# OLED_096_SH1101A_main.net
KiCad netlist of a schematic drawn in EAGLE
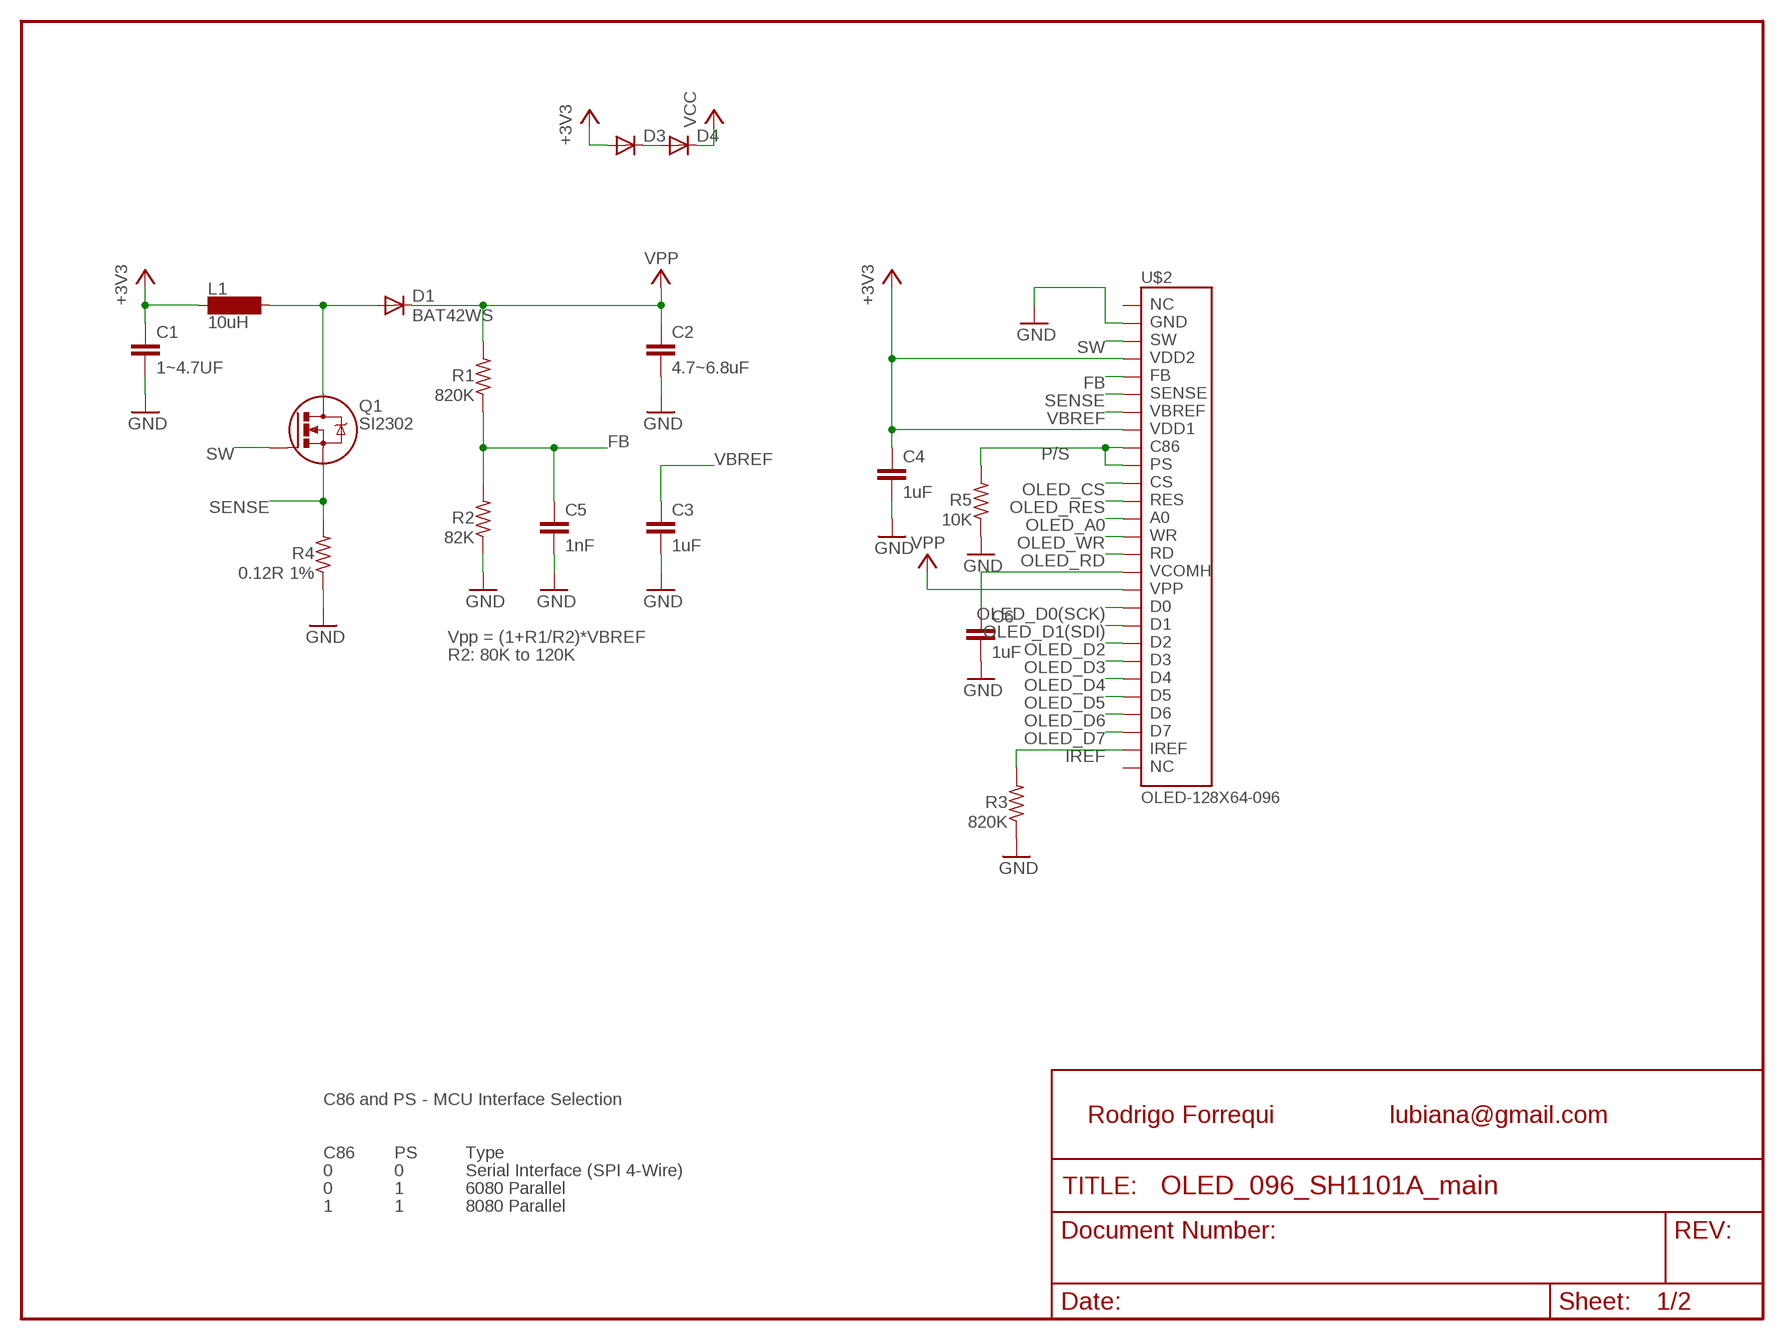
[diagram p0: schematic, sheet 1]
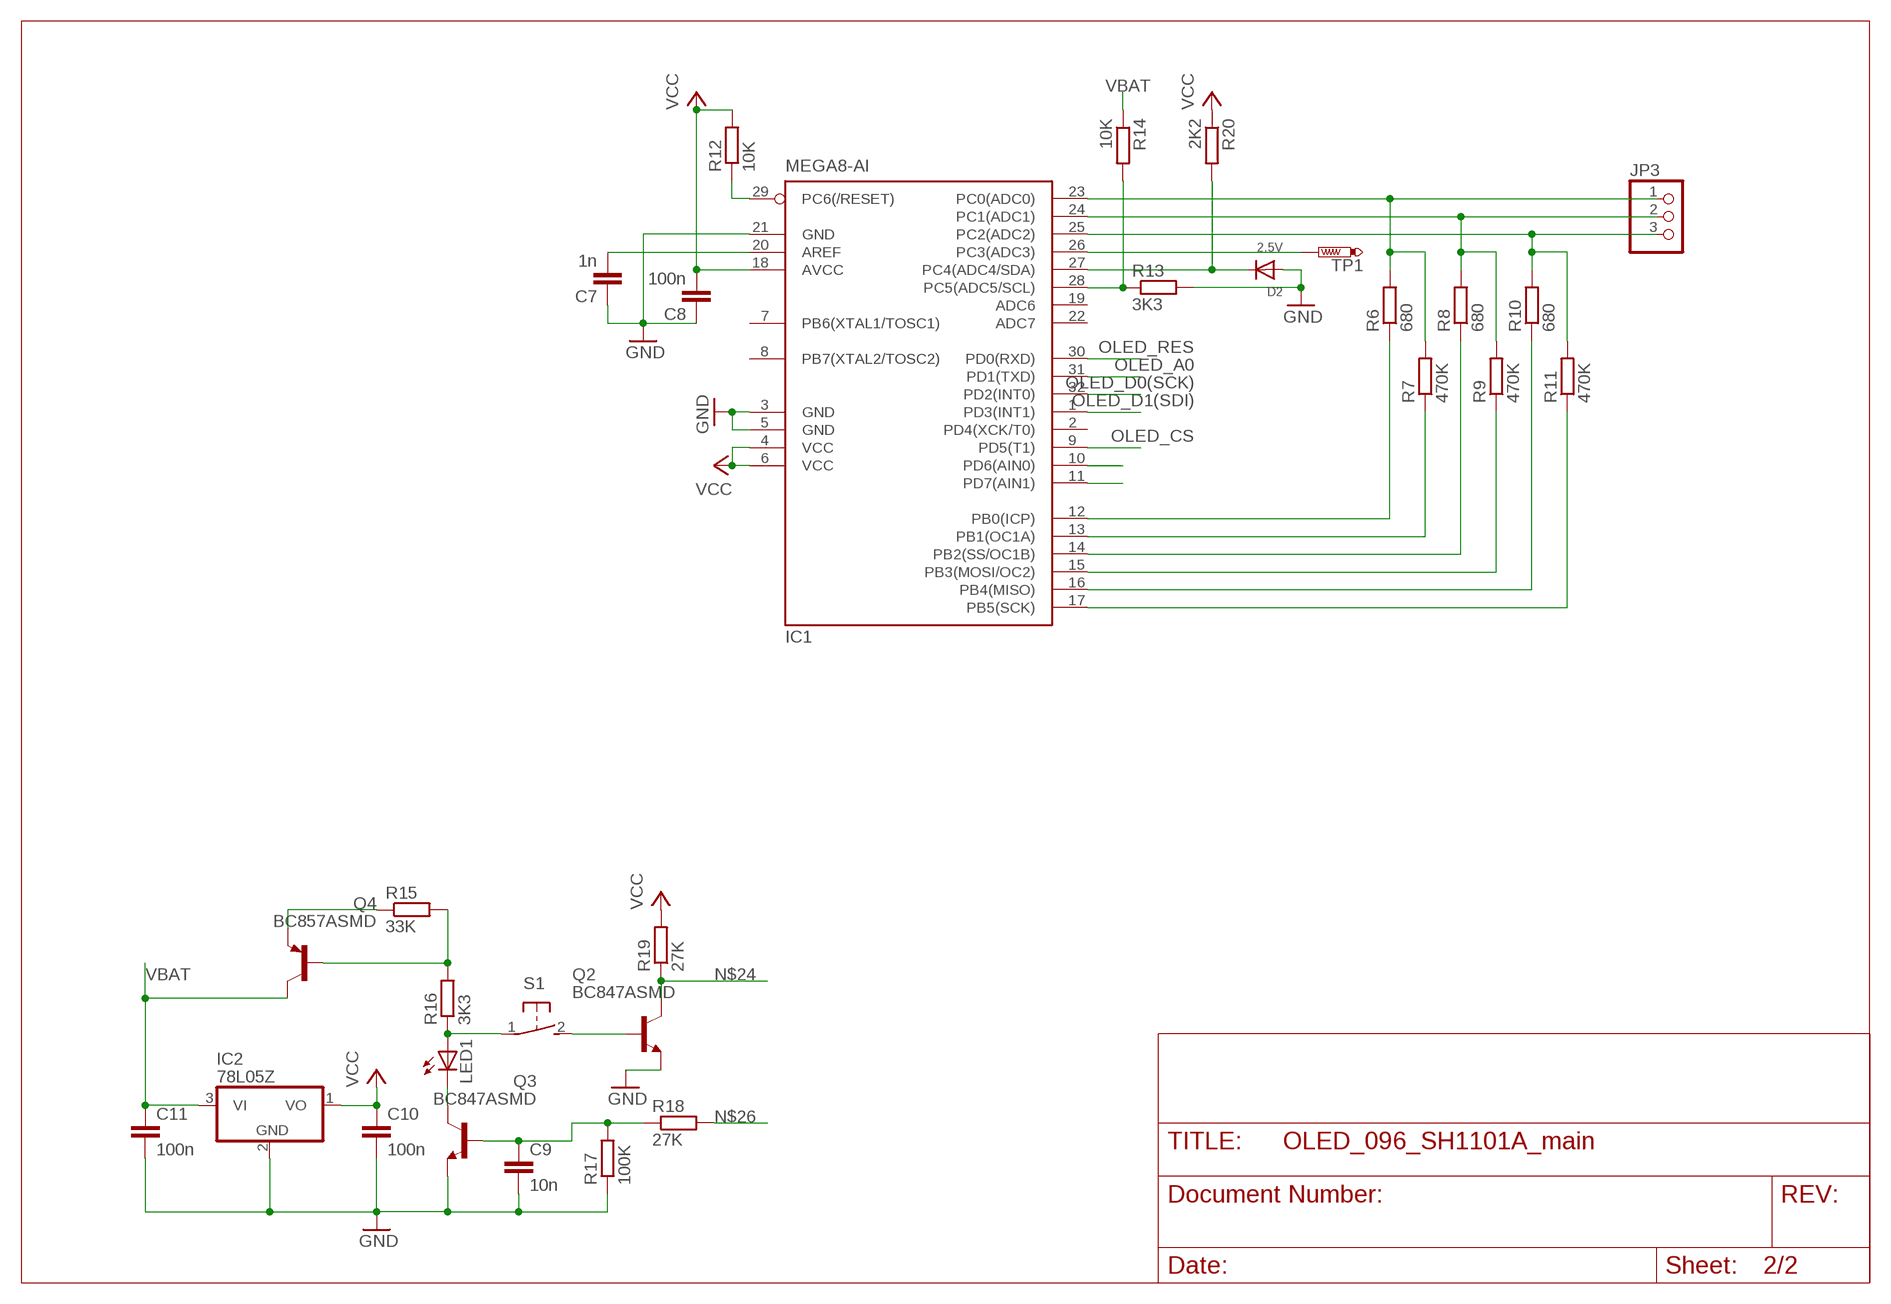
[diagram p1: schematic, sheet 2]

(export (version "E")
  (design (tool "Eeschema 10.0.6"))
  (components
    (comp (ref "C1")
      (value "1~4.7UF")
      (footprint "eagle-import:C0805")
      (libsource (lib "eagle-import") (part "C-EUC0805"))
    )
    (comp (ref "C2")
      (value "4.7~6.8uF")
      (footprint "eagle-import:C0805")
      (libsource (lib "eagle-import") (part "C-EUC0805"))
    )
    (comp (ref "C3")
      (value "1uF")
      (footprint "eagle-import:C0805")
      (libsource (lib "eagle-import") (part "C-EUC0805"))
    )
    (comp (ref "C4")
      (value "1uF")
      (footprint "eagle-import:C0805")
      (libsource (lib "eagle-import") (part "C-EUC0805"))
    )
    (comp (ref "C5")
      (value "1nF")
      (footprint "eagle-import:C0805")
      (libsource (lib "eagle-import") (part "C-EUC0805"))
    )
    (comp (ref "C6")
      (value "1uF")
      (footprint "eagle-import:C0805")
      (libsource (lib "eagle-import") (part "C-EUC0805"))
    )
    (comp (ref "D1")
      (value "BAT42WS")
      (footprint "eagle-import:SOD-323")
      (libsource (lib "eagle-import") (part "DIODESOD"))
    )
    (comp (ref "D3")
      (value "DIODE-MINIMELF")
      (footprint "eagle-import:MINIMELF")
      (libsource (lib "eagle-import") (part "DIODE-MINIMELF"))
    )
    (comp (ref "D4")
      (value "DIODE-MINIMELF")
      (footprint "eagle-import:MINIMELF")
      (libsource (lib "eagle-import") (part "DIODE-MINIMELF"))
    )
    (comp (ref "L1")
      (value "10uH")
      (footprint "eagle-import:LPO4812")
      (libsource (lib "eagle-import") (part "LPO4812"))
    )
    (comp (ref "Q1")
      (value "SI2302")
      (footprint "eagle-import:SOT23-3")
      (libsource (lib "eagle-import") (part "MOSFET-NCHANNELSMD"))
    )
    (comp (ref "R1")
      (value "820K")
      (footprint "eagle-import:R0805")
      (libsource (lib "eagle-import") (part "R-US_R0805"))
    )
    (comp (ref "R2")
      (value "82K")
      (footprint "eagle-import:R0805")
      (libsource (lib "eagle-import") (part "R-US_R0805"))
    )
    (comp (ref "R3")
      (value "820K")
      (footprint "eagle-import:R0805")
      (libsource (lib "eagle-import") (part "R-US_R0805"))
    )
    (comp (ref "R4")
      (value "0.12R 1%")
      (footprint "eagle-import:M1206")
      (libsource (lib "eagle-import") (part "R-US_M1206"))
    )
    (comp (ref "R5")
      (value "10K")
      (footprint "eagle-import:R0805")
      (libsource (lib "eagle-import") (part "R-US_R0805"))
    )
    (comp (ref "U$2")
      (value "OLED-128X64-096")
      (footprint "eagle-import:UG-2864AMBAG01")
      (libsource (lib "eagle-import") (part "OLED-128X64-096"))
    )
    (comp (ref "C7")
      (value "1n")
      (footprint "eagle-import:C0805")
      (libsource (lib "eagle-import") (part "resistor_C-EUC0805"))
    )
    (comp (ref "C8")
      (value "100n")
      (footprint "eagle-import:C0805")
      (libsource (lib "eagle-import") (part "resistor_C-EUC0805"))
    )
    (comp (ref "C9")
      (value "10n")
      (footprint "eagle-import:C0805")
      (libsource (lib "eagle-import") (part "resistor_C-EUC0805"))
    )
    (comp (ref "C10")
      (value "100n")
      (footprint "eagle-import:C0805")
      (libsource (lib "eagle-import") (part "resistor_C-EUC0805"))
    )
    (comp (ref "C11")
      (value "100n")
      (footprint "eagle-import:C0805")
      (libsource (lib "eagle-import") (part "resistor_C-EUC0805"))
    )
    (comp (ref "D2")
      (value "2.5V")
      (footprint "eagle-import:SOD-523")
      (libsource (lib "eagle-import") (part "DIODESOD-523"))
    )
    (comp (ref "IC1")
      (value "MEGA8-AI")
      (footprint "eagle-import:TQFP32-08")
      (fields (field (name "MPN") "ATMEGA8-16AU"))
      (libsource (lib "eagle-import") (part "MEGA8-AI"))
    )
    (comp (ref "IC2")
      (value "78L05Z")
      (footprint "eagle-import:TO92")
      (libsource (lib "eagle-import") (part "78ZL05"))
    )
    (comp (ref "JP3")
      (value "PINHD-1X3")
      (footprint "eagle-import:1X03")
      (libsource (lib "eagle-import") (part "PINHD-1X3"))
    )
    (comp (ref "LED1")
      (value "LEDSML0603")
      (footprint "eagle-import:SML0603")
      (libsource (lib "eagle-import") (part "LEDSML0603"))
    )
    (comp (ref "Q2")
      (value "BC847ASMD")
      (footprint "eagle-import:SOT23")
      (libsource (lib "eagle-import") (part "BC847SMDA"))
    )
    (comp (ref "Q3")
      (value "BC847ASMD")
      (footprint "eagle-import:SOT23")
      (libsource (lib "eagle-import") (part "BC847SMDA"))
    )
    (comp (ref "Q4")
      (value "BC857ASMD")
      (footprint "eagle-import:SOT23-BEC")
      (libsource (lib "eagle-import") (part "BC857SMDA"))
    )
    (comp (ref "R6")
      (value "680")
      (footprint "eagle-import:R0805")
      (libsource (lib "eagle-import") (part "R-EU_R0805"))
    )
    (comp (ref "R7")
      (value "470K")
      (footprint "eagle-import:R0805")
      (libsource (lib "eagle-import") (part "R-EU_R0805"))
    )
    (comp (ref "R8")
      (value "680")
      (footprint "eagle-import:R0805")
      (libsource (lib "eagle-import") (part "R-EU_R0805"))
    )
    (comp (ref "R9")
      (value "470K")
      (footprint "eagle-import:R0805")
      (libsource (lib "eagle-import") (part "R-EU_R0805"))
    )
    (comp (ref "R10")
      (value "680")
      (footprint "eagle-import:R0805")
      (libsource (lib "eagle-import") (part "R-EU_R0805"))
    )
    (comp (ref "R11")
      (value "470K")
      (footprint "eagle-import:R0805")
      (libsource (lib "eagle-import") (part "R-EU_R0805"))
    )
    (comp (ref "R12")
      (value "10K")
      (footprint "eagle-import:R0805")
      (libsource (lib "eagle-import") (part "R-EU_R0805"))
    )
    (comp (ref "R13")
      (value "3K3")
      (footprint "eagle-import:R0805")
      (libsource (lib "eagle-import") (part "R-EU_R0805"))
    )
    (comp (ref "R14")
      (value "10K")
      (footprint "eagle-import:R0805")
      (libsource (lib "eagle-import") (part "R-EU_R0805"))
    )
    (comp (ref "R15")
      (value "33K")
      (footprint "eagle-import:R0805")
      (libsource (lib "eagle-import") (part "R-EU_R0805"))
    )
    (comp (ref "R16")
      (value "3K3")
      (footprint "eagle-import:R0805")
      (libsource (lib "eagle-import") (part "R-EU_R0805"))
    )
    (comp (ref "R17")
      (value "100K")
      (footprint "eagle-import:R0805")
      (libsource (lib "eagle-import") (part "R-EU_R0805"))
    )
    (comp (ref "R18")
      (value "27K")
      (footprint "eagle-import:R0805")
      (libsource (lib "eagle-import") (part "R-EU_R0805"))
    )
    (comp (ref "R19")
      (value "27K")
      (footprint "eagle-import:R0805")
      (libsource (lib "eagle-import") (part "R-EU_R0805"))
    )
    (comp (ref "R20")
      (value "2K2")
      (footprint "eagle-import:R0805")
      (libsource (lib "eagle-import") (part "R-EU_R0805"))
    )
    (comp (ref "S1")
      (value "31-XX")
      (footprint "eagle-import:B3F-31XX")
      (fields (field (name "MPN") "B3F-3100"))
      (libsource (lib "eagle-import") (part "31-XX"))
    )
    (comp (ref "TP1")
      (value "PTR1B1,27")
      (footprint "eagle-import:B1,27")
      (libsource (lib "eagle-import") (part "PTR1B1,27"))
    )
  )
  (nets
    (net (code "1") (name "+3V3") (class "Default")
      (node (ref "C1") (pin "1") (pinfunction "1_1") (pintype "passive"))
      (node (ref "C4") (pin "1") (pinfunction "1_1") (pintype "passive"))
      (node (ref "D3") (pin "A") (pinfunction "A_A") (pintype "passive"))
      (node (ref "L1") (pin "P$1") (pinfunction "1_P$1") (pintype "passive"))
      (node (ref "U$2") (pin "P$4") (pinfunction "P$4_P$4") (pintype "power_in"))
      (node (ref "U$2") (pin "P$8") (pinfunction "P$8_P$8") (pintype "power_in"))
    )
    (net (code "2") (name "FB") (class "Default")
      (node (ref "C5") (pin "1") (pinfunction "1_1") (pintype "passive"))
      (node (ref "R1") (pin "1") (pinfunction "1_1") (pintype "passive"))
      (node (ref "R2") (pin "2") (pinfunction "2_2") (pintype "passive"))
      (node (ref "U$2") (pin "P$5") (pinfunction "P$5_P$5") (pintype "bidirectional"))
    )
    (net (code "3") (name "GND") (class "Default")
      (node (ref "C1") (pin "2") (pinfunction "2_2") (pintype "passive"))
      (node (ref "C10") (pin "2") (pinfunction "2_2") (pintype "passive"))
      (node (ref "C11") (pin "2") (pinfunction "2_2") (pintype "passive"))
      (node (ref "C2") (pin "2") (pinfunction "2_2") (pintype "passive"))
      (node (ref "C3") (pin "2") (pinfunction "2_2") (pintype "passive"))
      (node (ref "C4") (pin "2") (pinfunction "2_2") (pintype "passive"))
      (node (ref "C5") (pin "2") (pinfunction "2_2") (pintype "passive"))
      (node (ref "C6") (pin "2") (pinfunction "2_2") (pintype "passive"))
      (node (ref "C7") (pin "1") (pinfunction "1_1") (pintype "passive"))
      (node (ref "C8") (pin "1") (pinfunction "1_1") (pintype "passive"))
      (node (ref "C9") (pin "2") (pinfunction "2_2") (pintype "passive"))
      (node (ref "D2") (pin "A") (pinfunction "A_A") (pintype "passive"))
      (node (ref "IC1") (pin "21") (pinfunction "GND_21") (pintype "power_in"))
      (node (ref "IC1") (pin "3") (pinfunction "GND_3") (pintype "power_in"))
      (node (ref "IC1") (pin "5") (pinfunction "GND_5") (pintype "power_in"))
      (node (ref "IC2") (pin "2") (pinfunction "GND_2") (pintype "passive"))
      (node (ref "Q2") (pin "2") (pinfunction "E_2") (pintype "passive"))
      (node (ref "Q3") (pin "2") (pinfunction "E_2") (pintype "passive"))
      (node (ref "R13") (pin "2") (pinfunction "2_2") (pintype "passive"))
      (node (ref "R17") (pin "1") (pinfunction "1_1") (pintype "passive"))
      (node (ref "R2") (pin "1") (pinfunction "1_1") (pintype "passive"))
      (node (ref "R3") (pin "1") (pinfunction "1_1") (pintype "passive"))
      (node (ref "R4") (pin "1") (pinfunction "1_1") (pintype "passive"))
      (node (ref "R5") (pin "1") (pinfunction "1_1") (pintype "passive"))
      (node (ref "U$2") (pin "P$2") (pinfunction "P$2_P$2") (pintype "power_in"))
    )
    (net (code "4") (name "IREF") (class "Default")
      (node (ref "R3") (pin "2") (pinfunction "2_2") (pintype "passive"))
      (node (ref "U$2") (pin "P$26") (pinfunction "P$26_P$26") (pintype "bidirectional"))
    )
    (net (code "5") (name "N$24") (class "Default")
      (node (ref "IC1") (pin "11") (pinfunction "PD7(AIN1)_11") (pintype "bidirectional"))
      (node (ref "Q2") (pin "3") (pinfunction "C_3") (pintype "passive"))
      (node (ref "R19") (pin "1") (pinfunction "1_1") (pintype "passive"))
    )
    (net (code "6") (name "N$26") (class "Default")
      (node (ref "IC1") (pin "10") (pinfunction "PD6(AIN0)_10") (pintype "bidirectional"))
      (node (ref "R18") (pin "2") (pinfunction "2_2") (pintype "passive"))
    )
    (net (code "7") (name "Net-(C6-Pad1)") (class "Default")
      (node (ref "C6") (pin "1") (pinfunction "1_1") (pintype "passive"))
      (node (ref "U$2") (pin "P$16") (pinfunction "P$16_P$16") (pintype "bidirectional"))
    )
    (net (code "8") (name "Net-(D1-A)") (class "Default")
      (node (ref "D1") (pin "2") (pinfunction "A_2") (pintype "passive"))
      (node (ref "L1") (pin "P$2") (pinfunction "2_P$2") (pintype "passive"))
      (node (ref "Q1") (pin "3") (pinfunction "D_3") (pintype "passive"))
    )
    (net (code "9") (name "Net-(D2-C)") (class "Default")
      (node (ref "D2") (pin "K") (pinfunction "C_K") (pintype "passive"))
      (node (ref "IC1") (pin "27") (pinfunction "PC4(ADC4/SDA)_27") (pintype "bidirectional"))
      (node (ref "R20") (pin "2") (pinfunction "2_2") (pintype "passive"))
    )
    (net (code "10") (name "Net-(D3-PadC)") (class "Default")
      (node (ref "D3") (pin "C") (pinfunction "C_C") (pintype "passive"))
      (node (ref "D4") (pin "A") (pinfunction "A_A") (pintype "passive"))
    )
    (net (code "11") (name "Net-(IC1-AREF)") (class "Default")
      (node (ref "C7") (pin "2") (pinfunction "2_2") (pintype "passive"))
      (node (ref "IC1") (pin "20") (pinfunction "AREF_20") (pintype "passive"))
    )
    (net (code "12") (name "Net-(IC1-PB0(ICP))") (class "Default")
      (node (ref "IC1") (pin "12") (pinfunction "PB0(ICP)_12") (pintype "bidirectional"))
      (node (ref "R6") (pin "1") (pinfunction "1_1") (pintype "passive"))
    )
    (net (code "13") (name "Net-(IC1-PB1(OC1A))") (class "Default")
      (node (ref "IC1") (pin "13") (pinfunction "PB1(OC1A)_13") (pintype "bidirectional"))
      (node (ref "R7") (pin "1") (pinfunction "1_1") (pintype "passive"))
    )
    (net (code "14") (name "Net-(IC1-PB2(SS{slash}OC1B))") (class "Default")
      (node (ref "IC1") (pin "14") (pinfunction "PB2(SS/OC1B)_14") (pintype "bidirectional"))
      (node (ref "R8") (pin "1") (pinfunction "1_1") (pintype "passive"))
    )
    (net (code "15") (name "Net-(IC1-PB3(MOSI{slash}OC2))") (class "Default")
      (node (ref "IC1") (pin "15") (pinfunction "PB3(MOSI/OC2)_15") (pintype "bidirectional"))
      (node (ref "R9") (pin "1") (pinfunction "1_1") (pintype "passive"))
    )
    (net (code "16") (name "Net-(IC1-PB4(MISO))") (class "Default")
      (node (ref "IC1") (pin "16") (pinfunction "PB4(MISO)_16") (pintype "bidirectional"))
      (node (ref "R10") (pin "1") (pinfunction "1_1") (pintype "passive"))
    )
    (net (code "17") (name "Net-(IC1-PB5(SCK))") (class "Default")
      (node (ref "IC1") (pin "17") (pinfunction "PB5(SCK)_17") (pintype "bidirectional"))
      (node (ref "R11") (pin "1") (pinfunction "1_1") (pintype "passive"))
    )
    (net (code "18") (name "Net-(IC1-PC0(ADC0))") (class "Default")
      (node (ref "IC1") (pin "23") (pinfunction "PC0(ADC0)_23") (pintype "bidirectional"))
      (node (ref "JP3") (pin "1") (pinfunction "1_1") (pintype "passive"))
      (node (ref "R6") (pin "2") (pinfunction "2_2") (pintype "passive"))
      (node (ref "R7") (pin "2") (pinfunction "2_2") (pintype "passive"))
    )
    (net (code "19") (name "Net-(IC1-PC1(ADC1))") (class "Default")
      (node (ref "IC1") (pin "24") (pinfunction "PC1(ADC1)_24") (pintype "bidirectional"))
      (node (ref "JP3") (pin "2") (pinfunction "2_2") (pintype "passive"))
      (node (ref "R8") (pin "2") (pinfunction "2_2") (pintype "passive"))
      (node (ref "R9") (pin "2") (pinfunction "2_2") (pintype "passive"))
    )
    (net (code "20") (name "Net-(IC1-PC2(ADC2))") (class "Default")
      (node (ref "IC1") (pin "25") (pinfunction "PC2(ADC2)_25") (pintype "bidirectional"))
      (node (ref "JP3") (pin "3") (pinfunction "3_3") (pintype "passive"))
      (node (ref "R10") (pin "2") (pinfunction "2_2") (pintype "passive"))
      (node (ref "R11") (pin "2") (pinfunction "2_2") (pintype "passive"))
    )
    (net (code "21") (name "Net-(IC1-PC3(ADC3))") (class "Default")
      (node (ref "IC1") (pin "26") (pinfunction "PC3(ADC3)_26") (pintype "bidirectional"))
      (node (ref "TP1") (pin "TP") (pinfunction "TP_TP") (pintype "input"))
    )
    (net (code "22") (name "Net-(IC1-PC5(ADC5{slash}SCL))") (class "Default")
      (node (ref "IC1") (pin "28") (pinfunction "PC5(ADC5/SCL)_28") (pintype "bidirectional"))
      (node (ref "R13") (pin "1") (pinfunction "1_1") (pintype "passive"))
      (node (ref "R14") (pin "2") (pinfunction "2_2") (pintype "passive"))
    )
    (net (code "23") (name "Net-(IC1-PC6({slash}RESET))") (class "Default")
      (node (ref "IC1") (pin "29") (pinfunction "PC6(/RESET)_29") (pintype "bidirectional"))
      (node (ref "R12") (pin "1") (pinfunction "1_1") (pintype "passive"))
    )
    (net (code "24") (name "Net-(Q2-B)") (class "Default")
      (node (ref "Q2") (pin "1") (pinfunction "B_1") (pintype "passive"))
      (node (ref "S1") (pin "2") (pinfunction "S_2") (pintype "passive"))
    )
    (net (code "25") (name "Net-(Q3-B)") (class "Default")
      (node (ref "C9") (pin "1") (pinfunction "1_1") (pintype "passive"))
      (node (ref "Q3") (pin "1") (pinfunction "B_1") (pintype "passive"))
      (node (ref "R17") (pin "2") (pinfunction "2_2") (pintype "passive"))
      (node (ref "R18") (pin "1") (pinfunction "1_1") (pintype "passive"))
    )
    (net (code "26") (name "Net-(Q3-C)") (class "Default")
      (node (ref "LED1") (pin "C") (pinfunction "C_C") (pintype "passive"))
      (node (ref "Q3") (pin "3") (pinfunction "C_3") (pintype "passive"))
    )
    (net (code "27") (name "Net-(Q4-PadB)") (class "Default")
      (node (ref "Q4") (pin "B") (pinfunction "B_B") (pintype "passive"))
      (node (ref "R15") (pin "2") (pinfunction "2_2") (pintype "passive"))
      (node (ref "R16") (pin "2") (pinfunction "2_2") (pintype "passive"))
    )
    (net (code "28") (name "Net-(Q4-PadE)") (class "Default")
      (node (ref "Q4") (pin "E") (pinfunction "E_E") (pintype "passive"))
      (node (ref "R15") (pin "1") (pinfunction "1_1") (pintype "passive"))
    )
    (net (code "29") (name "Net-(S1-P)") (class "Default")
      (node (ref "LED1") (pin "A") (pinfunction "A_A") (pintype "passive"))
      (node (ref "R16") (pin "1") (pinfunction "1_1") (pintype "passive"))
      (node (ref "S1") (pin "1") (pinfunction "P_1") (pintype "passive"))
    )
    (net (code "30") (name "OLED_A0") (class "Default")
      (node (ref "IC1") (pin "31") (pinfunction "PD1(TXD)_31") (pintype "bidirectional"))
      (node (ref "U$2") (pin "P$13") (pinfunction "P$13_P$13") (pintype "bidirectional"))
    )
    (net (code "31") (name "OLED_CS") (class "Default")
      (node (ref "IC1") (pin "9") (pinfunction "PD5(T1)_9") (pintype "bidirectional"))
      (node (ref "U$2") (pin "P$11") (pinfunction "P$11_P$11") (pintype "bidirectional"))
    )
    (net (code "32") (name "OLED_D0(SCK)") (class "Default")
      (node (ref "IC1") (pin "32") (pinfunction "PD2(INT0)_32") (pintype "bidirectional"))
      (node (ref "U$2") (pin "P$18") (pinfunction "P$18_P$18") (pintype "bidirectional"))
    )
    (net (code "33") (name "OLED_D1(SDI)") (class "Default")
      (node (ref "IC1") (pin "1") (pinfunction "PD3(INT1)_1") (pintype "bidirectional"))
      (node (ref "U$2") (pin "P$19") (pinfunction "P$19_P$19") (pintype "bidirectional"))
    )
    (net (code "34") (name "OLED_D2") (class "Default")
      (node (ref "U$2") (pin "P$20") (pinfunction "P$20_P$20") (pintype "bidirectional"))
    )
    (net (code "35") (name "OLED_D3") (class "Default")
      (node (ref "U$2") (pin "P$21") (pinfunction "P$21_P$21") (pintype "bidirectional"))
    )
    (net (code "36") (name "OLED_D4") (class "Default")
      (node (ref "U$2") (pin "P$22") (pinfunction "P$22_P$22") (pintype "bidirectional"))
    )
    (net (code "37") (name "OLED_D5") (class "Default")
      (node (ref "U$2") (pin "P$23") (pinfunction "P$23_P$23") (pintype "bidirectional"))
    )
    (net (code "38") (name "OLED_D6") (class "Default")
      (node (ref "U$2") (pin "P$24") (pinfunction "P$24_P$24") (pintype "bidirectional"))
    )
    (net (code "39") (name "OLED_D7") (class "Default")
      (node (ref "U$2") (pin "P$25") (pinfunction "P$25_P$25") (pintype "bidirectional"))
    )
    (net (code "40") (name "OLED_RD") (class "Default")
      (node (ref "U$2") (pin "P$15") (pinfunction "P$15_P$15") (pintype "bidirectional"))
    )
    (net (code "41") (name "OLED_RES") (class "Default")
      (node (ref "IC1") (pin "30") (pinfunction "PD0(RXD)_30") (pintype "bidirectional"))
      (node (ref "U$2") (pin "P$12") (pinfunction "P$12_P$12") (pintype "bidirectional"))
    )
    (net (code "42") (name "OLED_WR") (class "Default")
      (node (ref "U$2") (pin "P$14") (pinfunction "P$14_P$14") (pintype "bidirectional"))
    )
    (net (code "43") (name "P{slash}S") (class "Default")
      (node (ref "R5") (pin "2") (pinfunction "2_2") (pintype "passive"))
      (node (ref "U$2") (pin "P$10") (pinfunction "P$10_P$10") (pintype "bidirectional"))
      (node (ref "U$2") (pin "P$9") (pinfunction "P$9_P$9") (pintype "bidirectional"))
    )
    (net (code "44") (name "SENSE") (class "Default")
      (node (ref "Q1") (pin "2") (pinfunction "S_2") (pintype "passive"))
      (node (ref "R4") (pin "2") (pinfunction "2_2") (pintype "passive"))
      (node (ref "U$2") (pin "P$6") (pinfunction "P$6_P$6") (pintype "bidirectional"))
    )
    (net (code "45") (name "SW") (class "Default")
      (node (ref "Q1") (pin "1") (pinfunction "G_1") (pintype "passive"))
      (node (ref "U$2") (pin "P$3") (pinfunction "P$3_P$3") (pintype "bidirectional"))
    )
    (net (code "46") (name "VBAT") (class "Default")
      (node (ref "C11") (pin "1") (pinfunction "1_1") (pintype "passive"))
      (node (ref "IC2") (pin "3") (pinfunction "VI_3") (pintype "input"))
      (node (ref "Q4") (pin "C") (pinfunction "C_C") (pintype "passive"))
      (node (ref "R14") (pin "1") (pinfunction "1_1") (pintype "passive"))
    )
    (net (code "47") (name "VBREF") (class "Default")
      (node (ref "C3") (pin "1") (pinfunction "1_1") (pintype "passive"))
      (node (ref "U$2") (pin "P$7") (pinfunction "P$7_P$7") (pintype "bidirectional"))
    )
    (net (code "48") (name "VCC") (class "Default")
      (node (ref "C10") (pin "1") (pinfunction "1_1") (pintype "passive"))
      (node (ref "C2") (pin "1") (pinfunction "1_1") (pintype "passive"))
      (node (ref "C8") (pin "2") (pinfunction "2_2") (pintype "passive"))
      (node (ref "D1") (pin "1") (pinfunction "C_1") (pintype "passive"))
      (node (ref "D4") (pin "C") (pinfunction "C_C") (pintype "passive"))
      (node (ref "IC1") (pin "18") (pinfunction "AVCC_18") (pintype "power_in"))
      (node (ref "IC1") (pin "4") (pinfunction "VCC_4") (pintype "power_in"))
      (node (ref "IC1") (pin "6") (pinfunction "VCC_6") (pintype "power_in"))
      (node (ref "IC2") (pin "1") (pinfunction "VO_1") (pintype "passive"))
      (node (ref "R1") (pin "2") (pinfunction "2_2") (pintype "passive"))
      (node (ref "R12") (pin "2") (pinfunction "2_2") (pintype "passive"))
      (node (ref "R19") (pin "2") (pinfunction "2_2") (pintype "passive"))
      (node (ref "R20") (pin "1") (pinfunction "1_1") (pintype "passive"))
      (node (ref "U$2") (pin "P$17") (pinfunction "P$17_P$17") (pintype "power_in"))
    )
    (net (code "49") (name "unconnected-(IC1-ADC6-Pad19)") (class "Default")
      (node (ref "IC1") (pin "19") (pinfunction "ADC6_19") (pintype "bidirectional"))
    )
    (net (code "50") (name "unconnected-(IC1-ADC7-Pad22)") (class "Default")
      (node (ref "IC1") (pin "22") (pinfunction "ADC7_22") (pintype "bidirectional"))
    )
    (net (code "51") (name "unconnected-(IC1-PB6(XTAL1{slash}TOSC1)-Pad7)") (class "Default")
      (node (ref "IC1") (pin "7") (pinfunction "PB6(XTAL1/TOSC1)_7") (pintype "bidirectional"))
    )
    (net (code "52") (name "unconnected-(IC1-PB7(XTAL2{slash}TOSC2)-Pad8)") (class "Default")
      (node (ref "IC1") (pin "8") (pinfunction "PB7(XTAL2/TOSC2)_8") (pintype "bidirectional"))
    )
    (net (code "53") (name "unconnected-(IC1-PD4(XCK{slash}T0)-Pad2)") (class "Default")
      (node (ref "IC1") (pin "2") (pinfunction "PD4(XCK/T0)_2") (pintype "bidirectional"))
    )
    (net (code "54") (name "unconnected-(U$2-PadP$1)") (class "Default")
      (node (ref "U$2") (pin "P$1") (pinfunction "P$1_P$1") (pintype "bidirectional"))
    )
    (net (code "55") (name "unconnected-(U$2-PadP$27)") (class "Default")
      (node (ref "U$2") (pin "P$27") (pinfunction "P$27_P$27") (pintype "bidirectional"))
    )
  )
)
